# rpi_breakout.net
KiCad netlist of a schematic drawn in EAGLE
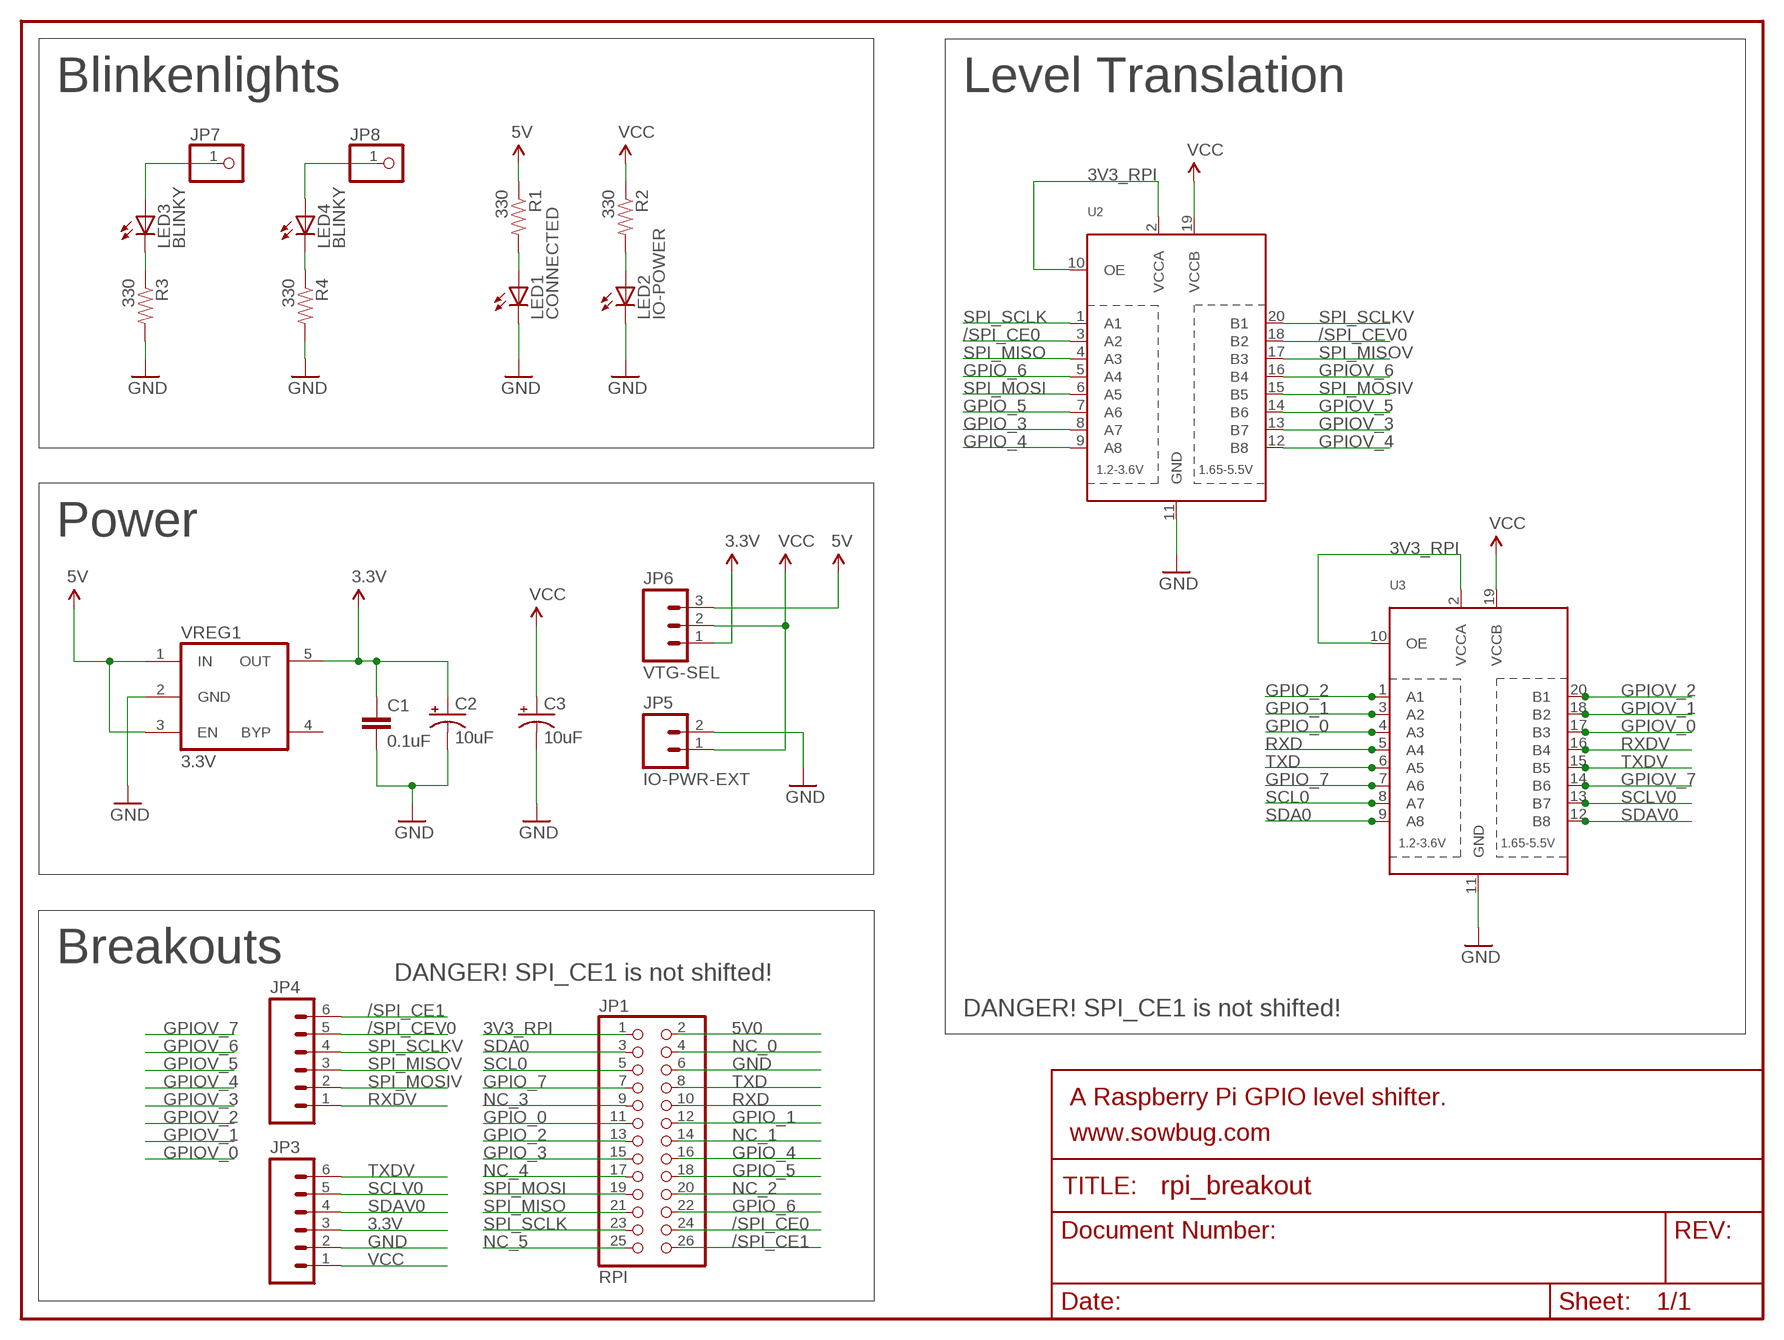
[diagram p0: schematic, sheet 1]

(export (version "E")
  (design (tool "Eeschema 10.0.6"))
  (components
    (comp (ref "C1")
      (value "0.1uF")
      (footprint "eagle-import:0805")
      (libsource (lib "eagle-import") (part "CAP0805"))
    )
    (comp (ref "C2")
      (value "10uF")
      (footprint "eagle-import:EIA3216")
      (libsource (lib "eagle-import") (part "CAP_POL1206"))
    )
    (comp (ref "C3")
      (value "10uF")
      (footprint "eagle-import:EIA3216")
      (libsource (lib "eagle-import") (part "CAP_POL1206"))
    )
    (comp (ref "JP1")
      (value "RPI")
      (footprint "eagle-import:2X13")
      (libsource (lib "eagle-import") (part "PINHD-2X13"))
    )
    (comp (ref "JP3")
      (value "M06FEMALE_LOCK")
      (footprint "eagle-import:1X06_FEMALE_LOCK.010")
      (libsource (lib "eagle-import") (part "M06FEMALE_LOCK"))
    )
    (comp (ref "JP4")
      (value "M06FEMALE_LOCK")
      (footprint "eagle-import:1X06_FEMALE_LOCK.010")
      (libsource (lib "eagle-import") (part "M06FEMALE_LOCK"))
    )
    (comp (ref "JP5")
      (value "IO-PWR-EXT")
      (footprint "eagle-import:1X02")
      (libsource (lib "eagle-import") (part "M02PTH"))
    )
    (comp (ref "JP6")
      (value "VTG-SEL")
      (footprint "eagle-import:1X03")
      (libsource (lib "eagle-import") (part "M03PTH"))
    )
    (comp (ref "JP7")
      (value "PINHD-1X1CB")
      (footprint "eagle-import:1X01-CLEANBIG")
      (libsource (lib "eagle-import") (part "PINHD-1X1CB"))
    )
    (comp (ref "JP8")
      (value "PINHD-1X1CB")
      (footprint "eagle-import:1X01-CLEANBIG")
      (libsource (lib "eagle-import") (part "PINHD-1X1CB"))
    )
    (comp (ref "LED1")
      (value "CONNECTED")
      (footprint "eagle-import:CHIPLED_0805")
      (libsource (lib "eagle-import") (part "LEDCHIPLED_0805"))
    )
    (comp (ref "LED2")
      (value "IO-POWER")
      (footprint "eagle-import:CHIPLED_0805")
      (libsource (lib "eagle-import") (part "LEDCHIPLED_0805"))
    )
    (comp (ref "LED3")
      (value "BLINKY")
      (footprint "eagle-import:CHIPLED_0805")
      (libsource (lib "eagle-import") (part "LEDCHIPLED_0805"))
    )
    (comp (ref "LED4")
      (value "BLINKY")
      (footprint "eagle-import:CHIPLED_0805")
      (libsource (lib "eagle-import") (part "LEDCHIPLED_0805"))
    )
    (comp (ref "R1")
      (value "330")
      (footprint "eagle-import:0805")
      (libsource (lib "eagle-import") (part "RESISTOR0805-RES"))
    )
    (comp (ref "R2")
      (value "330")
      (footprint "eagle-import:0805")
      (libsource (lib "eagle-import") (part "RESISTOR0805-RES"))
    )
    (comp (ref "R3")
      (value "330")
      (footprint "eagle-import:0805")
      (libsource (lib "eagle-import") (part "RESISTOR0805-RES"))
    )
    (comp (ref "R4")
      (value "330")
      (footprint "eagle-import:0805")
      (libsource (lib "eagle-import") (part "RESISTOR0805-RES"))
    )
    (comp (ref "U2")
      (value "TXB0108PWR")
      (footprint "eagle-import:TSSOP20")
      (libsource (lib "eagle-import") (part "TXB0108PWR"))
    )
    (comp (ref "U3")
      (value "TXB0108PWR")
      (footprint "eagle-import:TSSOP20")
      (libsource (lib "eagle-import") (part "TXB0108PWR"))
    )
    (comp (ref "VREG1")
      (value "3.3V")
      (footprint "eagle-import:SOT-23-5")
      (libsource (lib "eagle-import") (part "IC_VREG_5PINS-SOT-23-5"))
    )
  )
  (nets
    (net (code "1") (name "/3V3_RPI") (class "Default")
      (node (ref "JP1") (pin "1") (pinfunction "1_1") (pintype "passive"))
      (node (ref "U2") (pin "10") (pinfunction "OE_10") (pintype "bidirectional"))
      (node (ref "U2") (pin "2") (pinfunction "VCCA_2") (pintype "bidirectional"))
      (node (ref "U3") (pin "10") (pinfunction "OE_10") (pintype "bidirectional"))
      (node (ref "U3") (pin "2") (pinfunction "VCCA_2") (pintype "bidirectional"))
    )
    (net (code "2") (name "/5V0") (class "Default")
      (node (ref "JP1") (pin "2") (pinfunction "2_2") (pintype "passive"))
    )
    (net (code "3") (name "/GPIOV_0") (class "Default")
      (node (ref "U3") (pin "17") (pinfunction "B3_17") (pintype "bidirectional"))
    )
    (net (code "4") (name "/GPIOV_1") (class "Default")
      (node (ref "U3") (pin "18") (pinfunction "B2_18") (pintype "bidirectional"))
    )
    (net (code "5") (name "/GPIOV_2") (class "Default")
      (node (ref "U3") (pin "20") (pinfunction "B1_20") (pintype "bidirectional"))
    )
    (net (code "6") (name "/GPIOV_3") (class "Default")
      (node (ref "U2") (pin "13") (pinfunction "B7_13") (pintype "bidirectional"))
    )
    (net (code "7") (name "/GPIOV_4") (class "Default")
      (node (ref "U2") (pin "12") (pinfunction "B8_12") (pintype "bidirectional"))
    )
    (net (code "8") (name "/GPIOV_5") (class "Default")
      (node (ref "U2") (pin "14") (pinfunction "B6_14") (pintype "bidirectional"))
    )
    (net (code "9") (name "/GPIOV_6") (class "Default")
      (node (ref "U2") (pin "16") (pinfunction "B4_16") (pintype "bidirectional"))
    )
    (net (code "10") (name "/GPIOV_7") (class "Default")
      (node (ref "U3") (pin "14") (pinfunction "B6_14") (pintype "bidirectional"))
    )
    (net (code "11") (name "/GPIO_0") (class "Default")
      (node (ref "JP1") (pin "11") (pinfunction "11_11") (pintype "passive"))
      (node (ref "U3") (pin "4") (pinfunction "A3_4") (pintype "bidirectional"))
    )
    (net (code "12") (name "/GPIO_1") (class "Default")
      (node (ref "JP1") (pin "12") (pinfunction "12_12") (pintype "passive"))
      (node (ref "U3") (pin "3") (pinfunction "A2_3") (pintype "bidirectional"))
    )
    (net (code "13") (name "/GPIO_2") (class "Default")
      (node (ref "JP1") (pin "13") (pinfunction "13_13") (pintype "passive"))
      (node (ref "U3") (pin "1") (pinfunction "A1_1") (pintype "bidirectional"))
    )
    (net (code "14") (name "/GPIO_3") (class "Default")
      (node (ref "JP1") (pin "15") (pinfunction "15_15") (pintype "passive"))
      (node (ref "U2") (pin "8") (pinfunction "A7_8") (pintype "bidirectional"))
    )
    (net (code "15") (name "/GPIO_4") (class "Default")
      (node (ref "JP1") (pin "16") (pinfunction "16_16") (pintype "passive"))
      (node (ref "U2") (pin "9") (pinfunction "A8_9") (pintype "bidirectional"))
    )
    (net (code "16") (name "/GPIO_5") (class "Default")
      (node (ref "JP1") (pin "18") (pinfunction "18_18") (pintype "passive"))
      (node (ref "U2") (pin "7") (pinfunction "A6_7") (pintype "bidirectional"))
    )
    (net (code "17") (name "/GPIO_6") (class "Default")
      (node (ref "JP1") (pin "22") (pinfunction "22_22") (pintype "passive"))
      (node (ref "U2") (pin "5") (pinfunction "A4_5") (pintype "bidirectional"))
    )
    (net (code "18") (name "/GPIO_7") (class "Default")
      (node (ref "JP1") (pin "7") (pinfunction "7_7") (pintype "passive"))
      (node (ref "U3") (pin "7") (pinfunction "A6_7") (pintype "bidirectional"))
    )
    (net (code "19") (name "/NC_0") (class "Default")
      (node (ref "JP1") (pin "4") (pinfunction "4_4") (pintype "passive"))
    )
    (net (code "20") (name "/NC_1") (class "Default")
      (node (ref "JP1") (pin "14") (pinfunction "14_14") (pintype "passive"))
    )
    (net (code "21") (name "/NC_2") (class "Default")
      (node (ref "JP1") (pin "20") (pinfunction "20_20") (pintype "passive"))
    )
    (net (code "22") (name "/NC_3") (class "Default")
      (node (ref "JP1") (pin "9") (pinfunction "9_9") (pintype "passive"))
    )
    (net (code "23") (name "/NC_4") (class "Default")
      (node (ref "JP1") (pin "17") (pinfunction "17_17") (pintype "passive"))
    )
    (net (code "24") (name "/NC_5") (class "Default")
      (node (ref "JP1") (pin "25") (pinfunction "25_25") (pintype "passive"))
    )
    (net (code "25") (name "/RXD") (class "Default")
      (node (ref "JP1") (pin "10") (pinfunction "10_10") (pintype "passive"))
      (node (ref "U3") (pin "5") (pinfunction "A4_5") (pintype "bidirectional"))
    )
    (net (code "26") (name "/RXDV") (class "Default")
      (node (ref "JP4") (pin "1") (pinfunction "1_1") (pintype "passive"))
      (node (ref "U3") (pin "16") (pinfunction "B4_16") (pintype "bidirectional"))
    )
    (net (code "27") (name "/SCL0") (class "Default")
      (node (ref "JP1") (pin "5") (pinfunction "5_5") (pintype "passive"))
      (node (ref "U3") (pin "8") (pinfunction "A7_8") (pintype "bidirectional"))
    )
    (net (code "28") (name "/SCLV0") (class "Default")
      (node (ref "JP3") (pin "5") (pinfunction "5_5") (pintype "passive"))
      (node (ref "U3") (pin "13") (pinfunction "B7_13") (pintype "bidirectional"))
    )
    (net (code "29") (name "/SDA0") (class "Default")
      (node (ref "JP1") (pin "3") (pinfunction "3_3") (pintype "passive"))
      (node (ref "U3") (pin "9") (pinfunction "A8_9") (pintype "bidirectional"))
    )
    (net (code "30") (name "/SDAV0") (class "Default")
      (node (ref "JP3") (pin "4") (pinfunction "4_4") (pintype "passive"))
      (node (ref "U3") (pin "12") (pinfunction "B8_12") (pintype "bidirectional"))
    )
    (net (code "31") (name "/SPI_MISO") (class "Default")
      (node (ref "JP1") (pin "21") (pinfunction "21_21") (pintype "passive"))
      (node (ref "U2") (pin "4") (pinfunction "A3_4") (pintype "bidirectional"))
    )
    (net (code "32") (name "/SPI_MISOV") (class "Default")
      (node (ref "JP4") (pin "3") (pinfunction "3_3") (pintype "passive"))
      (node (ref "U2") (pin "17") (pinfunction "B3_17") (pintype "bidirectional"))
    )
    (net (code "33") (name "/SPI_MOSI") (class "Default")
      (node (ref "JP1") (pin "19") (pinfunction "19_19") (pintype "passive"))
      (node (ref "U2") (pin "6") (pinfunction "A5_6") (pintype "bidirectional"))
    )
    (net (code "34") (name "/SPI_MOSIV") (class "Default")
      (node (ref "JP4") (pin "2") (pinfunction "2_2") (pintype "passive"))
      (node (ref "U2") (pin "15") (pinfunction "B5_15") (pintype "bidirectional"))
    )
    (net (code "35") (name "/SPI_SCLK") (class "Default")
      (node (ref "JP1") (pin "23") (pinfunction "23_23") (pintype "passive"))
      (node (ref "U2") (pin "1") (pinfunction "A1_1") (pintype "bidirectional"))
    )
    (net (code "36") (name "/SPI_SCLKV") (class "Default")
      (node (ref "JP4") (pin "4") (pinfunction "4_4") (pintype "passive"))
      (node (ref "U2") (pin "20") (pinfunction "B1_20") (pintype "bidirectional"))
    )
    (net (code "37") (name "/TXD") (class "Default")
      (node (ref "JP1") (pin "8") (pinfunction "8_8") (pintype "passive"))
      (node (ref "U3") (pin "6") (pinfunction "A5_6") (pintype "bidirectional"))
    )
    (net (code "38") (name "/TXDV") (class "Default")
      (node (ref "JP3") (pin "6") (pinfunction "6_6") (pintype "passive"))
      (node (ref "U3") (pin "15") (pinfunction "B5_15") (pintype "bidirectional"))
    )
    (net (code "39") (name "/{slash}SPI_CE0") (class "Default")
      (node (ref "JP1") (pin "24") (pinfunction "24_24") (pintype "passive"))
      (node (ref "U2") (pin "3") (pinfunction "A2_3") (pintype "bidirectional"))
    )
    (net (code "40") (name "/{slash}SPI_CE1") (class "Default")
      (node (ref "JP1") (pin "26") (pinfunction "26_26") (pintype "passive"))
      (node (ref "JP4") (pin "6") (pinfunction "6_6") (pintype "passive"))
    )
    (net (code "41") (name "/{slash}SPI_CEV0") (class "Default")
      (node (ref "JP4") (pin "5") (pinfunction "5_5") (pintype "passive"))
      (node (ref "U2") (pin "18") (pinfunction "B2_18") (pintype "bidirectional"))
    )
    (net (code "42") (name "3.3V") (class "Default")
      (node (ref "C1") (pin "1") (pinfunction "1_1") (pintype "passive"))
      (node (ref "C2") (pin "A") (pinfunction "+_A") (pintype "passive"))
      (node (ref "JP3") (pin "3") (pinfunction "3_3") (pintype "passive"))
      (node (ref "JP6") (pin "1") (pinfunction "1_1") (pintype "passive"))
      (node (ref "VREG1") (pin "5") (pinfunction "OUT_5") (pintype "bidirectional"))
    )
    (net (code "43") (name "5V") (class "Default")
      (node (ref "JP6") (pin "3") (pinfunction "3_3") (pintype "passive"))
      (node (ref "R1") (pin "1") (pinfunction "1_1") (pintype "passive"))
      (node (ref "VREG1") (pin "1") (pinfunction "IN_1") (pintype "bidirectional"))
      (node (ref "VREG1") (pin "3") (pinfunction "EN_3") (pintype "bidirectional"))
    )
    (net (code "44") (name "GND") (class "Default")
      (node (ref "C1") (pin "2") (pinfunction "2_2") (pintype "passive"))
      (node (ref "C2") (pin "C") (pinfunction "-_C") (pintype "passive"))
      (node (ref "C3") (pin "C") (pinfunction "-_C") (pintype "passive"))
      (node (ref "JP1") (pin "6") (pinfunction "6_6") (pintype "passive"))
      (node (ref "JP3") (pin "2") (pinfunction "2_2") (pintype "passive"))
      (node (ref "JP5") (pin "2") (pinfunction "2_2") (pintype "passive"))
      (node (ref "LED1") (pin "C") (pinfunction "C_C") (pintype "passive"))
      (node (ref "LED2") (pin "C") (pinfunction "C_C") (pintype "passive"))
      (node (ref "R3") (pin "2") (pinfunction "2_2") (pintype "passive"))
      (node (ref "R4") (pin "2") (pinfunction "2_2") (pintype "passive"))
      (node (ref "U2") (pin "11") (pinfunction "GND_11") (pintype "bidirectional"))
      (node (ref "U3") (pin "11") (pinfunction "GND_11") (pintype "bidirectional"))
      (node (ref "VREG1") (pin "2") (pinfunction "GND_2") (pintype "bidirectional"))
    )
    (net (code "45") (name "Net-(JP7-Pad1)") (class "Default")
      (node (ref "JP7") (pin "1") (pinfunction "1_1") (pintype "passive"))
      (node (ref "LED3") (pin "A") (pinfunction "A_A") (pintype "passive"))
    )
    (net (code "46") (name "Net-(JP8-Pad1)") (class "Default")
      (node (ref "JP8") (pin "1") (pinfunction "1_1") (pintype "passive"))
      (node (ref "LED4") (pin "A") (pinfunction "A_A") (pintype "passive"))
    )
    (net (code "47") (name "Net-(LED1-PadA)") (class "Default")
      (node (ref "LED1") (pin "A") (pinfunction "A_A") (pintype "passive"))
      (node (ref "R1") (pin "2") (pinfunction "2_2") (pintype "passive"))
    )
    (net (code "48") (name "Net-(LED2-PadA)") (class "Default")
      (node (ref "LED2") (pin "A") (pinfunction "A_A") (pintype "passive"))
      (node (ref "R2") (pin "2") (pinfunction "2_2") (pintype "passive"))
    )
    (net (code "49") (name "Net-(LED3-PadC)") (class "Default")
      (node (ref "LED3") (pin "C") (pinfunction "C_C") (pintype "passive"))
      (node (ref "R3") (pin "1") (pinfunction "1_1") (pintype "passive"))
    )
    (net (code "50") (name "Net-(LED4-PadC)") (class "Default")
      (node (ref "LED4") (pin "C") (pinfunction "C_C") (pintype "passive"))
      (node (ref "R4") (pin "1") (pinfunction "1_1") (pintype "passive"))
    )
    (net (code "51") (name "VCC") (class "Default")
      (node (ref "C3") (pin "A") (pinfunction "+_A") (pintype "passive"))
      (node (ref "JP3") (pin "1") (pinfunction "1_1") (pintype "passive"))
      (node (ref "JP5") (pin "1") (pinfunction "1_1") (pintype "passive"))
      (node (ref "JP6") (pin "2") (pinfunction "2_2") (pintype "passive"))
      (node (ref "R2") (pin "1") (pinfunction "1_1") (pintype "passive"))
      (node (ref "U2") (pin "19") (pinfunction "VCCB_19") (pintype "bidirectional"))
      (node (ref "U3") (pin "19") (pinfunction "VCCB_19") (pintype "bidirectional"))
    )
    (net (code "52") (name "unconnected-(VREG1-BYP-Pad4)") (class "Default")
      (node (ref "VREG1") (pin "4") (pinfunction "BYP_4") (pintype "bidirectional"))
    )
  )
)
